# RF-learn-command-1relay.net
KiCad netlist of a schematic drawn in Altium Designer
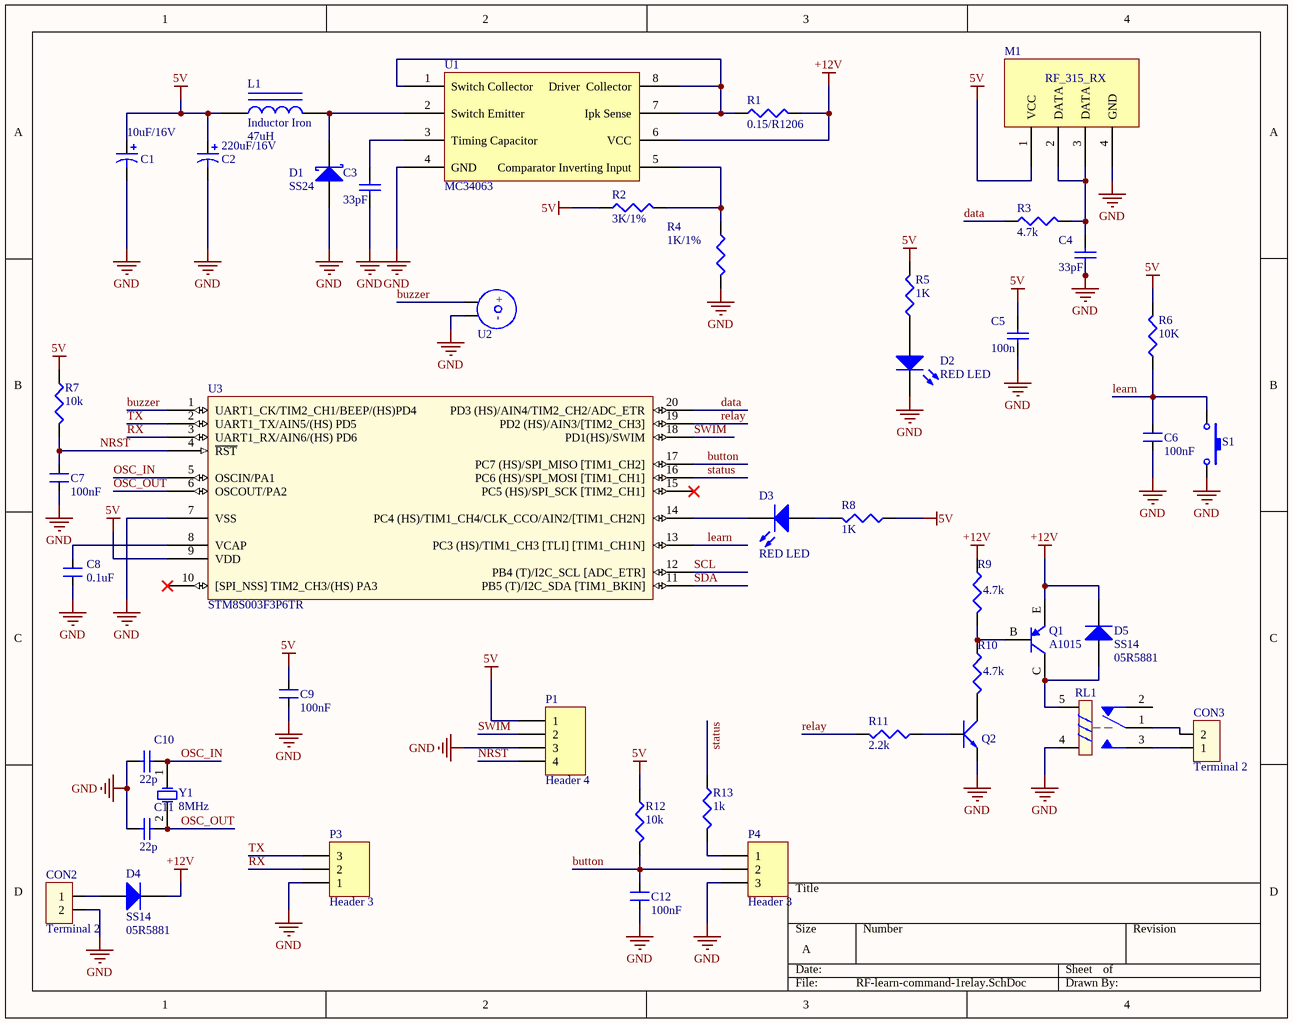
[diagram p0: RF-learn-command-1relay.SchDoc]

(export (version "E")
  (design (tool "Eeschema 10.0.6"))
  (components
    (comp (ref "C1")
      (value "10uF/16V")
      (footprint "Capacitor:C1206")
      (description "Polarized Capacitor (Surface Mount)")
      (fields (field (name "PUBLISHER") "Altium Limited"))
      (libsource (lib "Miscellaneous Devices") (part "Cap Pol3"))
    )
    (comp (ref "C2")
      (value "220uF/16V")
      (footprint "CAPACITOR SIZE_D(D6.6)")
      (description "Polarized Capacitor (Surface Mount)")
      (fields (field (name "PUBLISHER") "Altium Limited"))
      (libsource (lib "Miscellaneous Devices") (part "Cap Pol3"))
    )
    (comp (ref "C3")
      (value "33pF")
      (footprint "ST:CM 0805")
      (description "Capacitor 100n 16V 0603")
      (fields (field (name "PUBLISHER") "Altium Limited"))
      (libsource (lib "Capacitor") (part "Cap Semi"))
    )
    (comp (ref "C4")
      (value "33pF")
      (footprint "ST:CM 0805")
      (description "Capacitor 100n 16V 0603")
      (fields (field (name "PUBLISHER") "Altium Limited"))
      (libsource (lib "Capacitor") (part "Cap Semi"))
    )
    (comp (ref "C5")
      (value "100n")
      (footprint "ST:CM 0805")
      (description "Capacitor 100n 16V 0603")
      (fields (field (name "PUBLISHER") "Altium Limited"))
      (libsource (lib "Capacitor") (part "Cap Semi"))
    )
    (comp (ref "C6")
      (value "100nF")
      (footprint "ST:CM 0805")
      (description "SMD Ceramic  Capacitor")
      (fields (field (name "VOLTAGE") "50V") (field (name "TOLERANCE") "10%"))
      (libsource (lib "ST") (part "CM Ceramic"))
    )
    (comp (ref "C7")
      (value "100nF")
      (footprint "ST:CM 0805")
      (description "SMD Ceramic  Capacitor")
      (fields (field (name "VOLTAGE") "50V") (field (name "TOLERANCE") "10%"))
      (libsource (lib "ST") (part "CM Ceramic"))
    )
    (comp (ref "C8")
      (value "0.1uF")
      (footprint "ST:CM 0805")
      (description "SMD Ceramic  Capacitor")
      (fields (field (name "VOLTAGE") "50V") (field (name "TOLERANCE") "10%"))
      (libsource (lib "ST") (part "CM Ceramic"))
    )
    (comp (ref "C9")
      (value "100nF")
      (footprint "ST:CM 0805")
      (description "SMD Ceramic  Capacitor")
      (fields (field (name "VOLTAGE") "50V") (field (name "TOLERANCE") "10%"))
      (libsource (lib "ST") (part "CM Ceramic"))
    )
    (comp (ref "C10")
      (value "22p")
      (footprint "ST:CM 0805")
      (description "Capacitor (Semiconductor SIM Model)")
      (fields (field (name "PUBLISHER") "Altium Limited"))
      (libsource (lib "Miscellaneous Devices") (part "Cap Semi"))
    )
    (comp (ref "C11")
      (value "22p")
      (footprint "ST:CM 0805")
      (description "Capacitor (Semiconductor SIM Model)")
      (fields (field (name "PUBLISHER") "Altium Limited"))
      (libsource (lib "Miscellaneous Devices") (part "Cap Semi"))
    )
    (comp (ref "C12")
      (value "100nF")
      (footprint "ST:CM 0805")
      (description "SMD Ceramic  Capacitor")
      (fields (field (name "VOLTAGE") "50V") (field (name "TOLERANCE") "10%"))
      (libsource (lib "ST") (part "CM Ceramic"))
    )
    (comp (ref "CON2")
      (value "Terminal 2")
      (footprint "Terminal 2 5.08")
      (libsource (lib "") (part "Terminal 2_1"))
    )
    (comp (ref "CON3")
      (value "Terminal 2")
      (footprint "domino-2pin-7.62")
      (libsource (lib "SS_Con") (part "Terminal 2"))
    )
    (comp (ref "D1")
      (value "SS24")
      (footprint "DO-214AA")
      (description "Schottky Diode")
      (fields (field (name "PUBLISHER") "Altium Limited"))
      (libsource (lib "Miscellaneous Devices") (part "D Schottky"))
    )
    (comp (ref "D2")
      (value "RED LED")
      (footprint "LED3mm-R")
      (description "LED SUPR RED CLR 0805 RT ANG SMD")
      (fields
        (field (name "DIGI-KEY PART NUMBER") "160-1469-2-ND")
        (field (name "MANUFACTURER") "Lite-On Inc")
        (field (name "PUBLISHER") "Altium Limited")
      )
      (libsource (lib "Miscellaneous Devices") (part "LED2"))
    )
    (comp (ref "D3")
      (value "RED LED")
      (footprint "LED3mm-G")
      (description "LED SUPR RED CLR 0805 RT ANG SMD")
      (fields
        (field (name "DIGI-KEY PART NUMBER") "160-1469-2-ND")
        (field (name "MANUFACTURER") "Lite-On Inc")
        (field (name "PUBLISHER") "Altium Limited")
      )
      (libsource (lib "Miscellaneous Devices") (part "LED2"))
    )
    (comp (ref "D4")
      (value "SS14")
      (footprint "DO-214AC (SMA)")
      (description "DIODE GEN PURPOSE 1000V 1A SMA")
      (fields
        (field (name "DIGI-KEY PART NUMBER") "641-1018-1-ND")
        (field (name "MANUFACTURER PART NUMBER") "CGRA4007-G")
        (field (name "SUPPLIER PART NUMBER 1") "05R5881")
        (field (name "PUBLISHER") "Altium Limited")
      )
      (libsource (lib "Miscellaneous Devices") (part "Diode"))
    )
    (comp (ref "D5")
      (value "SS14")
      (footprint "DO-214AC (SMA)")
      (description "DIODE GEN PURPOSE 1000V 1A SMA")
      (fields
        (field (name "DIGI-KEY PART NUMBER") "641-1018-1-ND")
        (field (name "MANUFACTURER PART NUMBER") "CGRA4007-G")
        (field (name "SUPPLIER PART NUMBER 1") "05R5881")
        (field (name "PUBLISHER") "Altium Limited")
      )
      (libsource (lib "Miscellaneous Devices") (part "Diode"))
    )
    (comp (ref "L1")
      (value "Inductor Iron")
      (footprint "4848")
      (description "Magnetic-Core Inductor")
      (fields (field (name "ALTIUM_VALUE") "47uH") (field (name "PUBLISHER") "Altium Limited"))
      (libsource (lib "Schematic") (part "Inductor Iron"))
    )
    (comp (ref "M1")
      (value "RF_315_RX")
      (footprint "module-lib:Module-RF-RX")
      (libsource (lib "module-lib") (part "ModuleRF-RX"))
    )
    (comp (ref "P1")
      (value "Header 4")
      (footprint "SS_Con:HDR1X4")
      (description "Header, 4-Pin")
      (fields (field (name "PUBLISHER") "Altium Limited"))
      (libsource (lib "SS_Con") (part "Header 4"))
    )
    (comp (ref "P3")
      (value "Header 3")
      (footprint "SS_Con:HDR1X3")
      (description "Header, 3-Pin")
      (fields (field (name "PUBLISHER") "Altium Limited"))
      (libsource (lib "SS_Con") (part "Header 3"))
    )
    (comp (ref "P4")
      (value "Header 3")
      (footprint "HEADER_3_W")
      (description "Header, 3-Pin")
      (fields (field (name "PUBLISHER") "Altium Limited"))
      (libsource (lib "") (part "Header 3_1"))
    )
    (comp (ref "Q1")
      (value "A1015")
      (footprint "SC-43-BCE")
      (libsource (lib "Transistor") (part "PNP Transistor"))
    )
    (comp (ref "Q2")
      (value "C1815")
      (footprint "2SC1815")
      (description "NPN SMD Transistor")
      (fields (field (name "MANUFACTURER") "Toshiba"))
      (libsource (lib "ST") (part "C1815"))
    )
    (comp (ref "R1")
      (value "0.15/R1206")
      (footprint "R1206")
      (description "Resistor 10k 0603")
      (fields (field (name "PUBLISHER") "Altium Limited"))
      (libsource (lib "Miscellaneous Devices") (part "Res3"))
    )
    (comp (ref "R2")
      (value "3K/1%")
      (footprint "R0805")
      (description "Resistor 10k 0603")
      (fields (field (name "PUBLISHER") "Altium Limited"))
      (libsource (lib "Miscellaneous Devices") (part "Res3"))
    )
    (comp (ref "R3")
      (value "4.7k")
      (footprint "R0805")
      (description "Resistor")
      (fields
        (field (name "MANUFACTURER") "Vishay / Draloric")
        (field (name "MANUFACTURER PART NUMBER") "RCV0805301KFKEA")
        (field (name "PUBLISHER") "Altium Limited")
      )
      (libsource (lib "altium-import") (part "root_0_Res3_"))
    )
    (comp (ref "R4")
      (value "1K/1%")
      (footprint "R0805")
      (description "Resistor 10k 0603")
      (fields (field (name "PUBLISHER") "Altium Limited"))
      (libsource (lib "Miscellaneous Devices") (part "Res3"))
    )
    (comp (ref "R5")
      (value "1K")
      (footprint "R0805")
      (description "Resistor 10k 0603")
      (fields (field (name "PUBLISHER") "Altium Limited"))
      (libsource (lib "Miscellaneous Devices") (part "Res3"))
    )
    (comp (ref "R6")
      (value "10K")
      (footprint "R0805")
      (description "Resistor 10k 0603")
      (fields (field (name "PUBLISHER") "Altium Limited"))
      (libsource (lib "Miscellaneous Devices") (part "Res3"))
    )
    (comp (ref "R7")
      (value "10k")
      (footprint "R0805")
      (description "Resistor")
      (fields
        (field (name "MANUFACTURER") "Vishay / Draloric")
        (field (name "MANUFACTURER PART NUMBER") "RCV0805301KFKEA")
        (field (name "PUBLISHER") "Altium Limited")
      )
      (libsource (lib "altium-import") (part "root_3_Res3_"))
    )
    (comp (ref "R8")
      (value "1K")
      (footprint "R0805")
      (description "Resistor 10k 0603")
      (fields (field (name "PUBLISHER") "Altium Limited"))
      (libsource (lib "Miscellaneous Devices") (part "Res3"))
    )
    (comp (ref "R9")
      (value "4.7k")
      (footprint "R0805")
      (description "Resistor")
      (fields
        (field (name "MANUFACTURER") "Vishay / Draloric")
        (field (name "MANUFACTURER PART NUMBER") "RCV0805301KFKEA")
        (field (name "PUBLISHER") "Altium Limited")
      )
      (libsource (lib "altium-import") (part "root_3_Res3_"))
    )
    (comp (ref "R10")
      (value "4.7k")
      (footprint "R0805")
      (description "Resistor")
      (fields
        (field (name "MANUFACTURER") "Vishay / Draloric")
        (field (name "MANUFACTURER PART NUMBER") "RCV0805301KFKEA")
        (field (name "PUBLISHER") "Altium Limited")
      )
      (libsource (lib "altium-import") (part "root_3_Res3_"))
    )
    (comp (ref "R11")
      (value "2.2k")
      (footprint "R0805")
      (description "Resistor")
      (fields
        (field (name "MANUFACTURER") "Vishay / Draloric")
        (field (name "MANUFACTURER PART NUMBER") "RCV0805301KFKEA")
        (field (name "PUBLISHER") "Altium Limited")
      )
      (libsource (lib "altium-import") (part "root_2_Res3_"))
    )
    (comp (ref "R12")
      (value "10k")
      (footprint "R0805")
      (description "Resistor")
      (fields
        (field (name "MANUFACTURER") "Vishay / Draloric")
        (field (name "MANUFACTURER PART NUMBER") "RCV0805301KFKEA")
        (field (name "PUBLISHER") "Altium Limited")
      )
      (libsource (lib "altium-import") (part "root_3_Res3_"))
    )
    (comp (ref "R13")
      (value "1k")
      (footprint "R0805")
      (description "Resistor")
      (fields
        (field (name "MANUFACTURER") "Vishay / Draloric")
        (field (name "MANUFACTURER PART NUMBER") "RCV0805301KFKEA")
        (field (name "PUBLISHER") "Altium Limited")
      )
      (libsource (lib "altium-import") (part "root_3_Res3_"))
    )
    (comp (ref "RL1")
      (value "Relay SPDT, 10A, 12V")
      (footprint "RL-SLA-24/12VDC-SL-C")
      (description "Relay SPDT,10A - 12VDC 5 Pin")
      (libsource (lib "nhantt-relay-lib") (part "Relay 1"))
    )
    (comp (ref "S1")
      (value "SW-SMD")
      (footprint "Button Tactile Switch")
      (description "Switch")
      (fields (field (name "PUBLISHER") "Altium Limited"))
      (libsource (lib "Schematic") (part "SW-SMD"))
    )
    (comp (ref "U1")
      (value "MC34063")
      (footprint "SO8-150mil")
      (libsource (lib "General IC") (part "MC34063"))
    )
    (comp (ref "U2") (value "Buzzer") (footprint "Buzzer") (libsource (lib "ST") (part "Buzzer")))
    (comp (ref "U3")
      (value "STM8S003F3P6TR")
      (footprint "SSOP-20")
      (description "MCU")
      (fields (field (name "MANUFACTURER") "STMicroelectronics"))
      (libsource (lib "mcu-lib") (part "STM8S003F3"))
    )
    (comp (ref "Y1")
      (value "8MHz")
      (footprint "XTAL:HC49/US-SMD")
      (description "Crystal Oscillator")
      (fields (field (name "PUBLISHER") "Altium Limited"))
      (libsource (lib "Miscellaneous Devices") (part "XTAL"))
    )
  )
  (nets
    (net (code "1") (name "+12V") (class "Default")
      (node (ref "D4") (pin "2") (pinfunction "K_2") (pintype "passive"))
      (node (ref "D5") (pin "2") (pinfunction "K_2") (pintype "passive"))
      (node (ref "Q1") (pin "E") (pinfunction "E_E") (pintype "passive"))
      (node (ref "R1") (pin "2") (pinfunction "2_2") (pintype "passive"))
      (node (ref "R9") (pin "1") (pinfunction "1_1") (pintype "passive"))
      (node (ref "U1") (pin "6") (pinfunction "VCC_6") (pintype "passive"))
    )
    (net (code "2") (name "/NRST") (class "Default")
      (node (ref "C7") (pin "2") (pinfunction "2_2") (pintype "passive"))
      (node (ref "P1") (pin "4") (pinfunction "4_4") (pintype "passive"))
      (node (ref "R7") (pin "2") (pinfunction "2_2") (pintype "passive"))
      (node (ref "U3") (pin "4") (pinfunction "~{RST}_4") (pintype "input"))
    )
    (net (code "3") (name "/OSC_IN") (class "Default")
      (node (ref "C10") (pin "2") (pinfunction "2_2") (pintype "passive"))
      (node (ref "U3") (pin "5") (pinfunction "OSCIN/PA1_5") (pintype "bidirectional"))
      (node (ref "Y1") (pin "1") (pinfunction "OSC1_1") (pintype "passive"))
    )
    (net (code "4") (name "/OSC_OUT") (class "Default")
      (node (ref "C11") (pin "2") (pinfunction "2_2") (pintype "passive"))
      (node (ref "U3") (pin "6") (pinfunction "OSCOUT/PA2_6") (pintype "bidirectional"))
      (node (ref "Y1") (pin "2") (pinfunction "OSC2_2") (pintype "passive"))
    )
    (net (code "5") (name "/RX") (class "Default")
      (node (ref "P3") (pin "2") (pinfunction "2_2") (pintype "passive"))
      (node (ref "U3") (pin "3") (pinfunction "UART1_RX/AIN6/(HS)_PD6_3") (pintype "bidirectional"))
    )
    (net (code "6") (name "/SCL") (class "Default")
      (node (ref "U3") (pin "12") (pinfunction "PB4_(T)/I2C_SCL_[ADC_ETR]_12") (pintype "bidirectional"))
    )
    (net (code "7") (name "/SDA") (class "Default")
      (node (ref "U3") (pin "11") (pinfunction "PB5_(T)/I2C_SDA_[TIM1_BKIN]_11") (pintype "bidirectional"))
    )
    (net (code "8") (name "/SWIM") (class "Default")
      (node (ref "P1") (pin "2") (pinfunction "2_2") (pintype "passive"))
      (node (ref "U3") (pin "18") (pinfunction "PD1(HS)/SWIM_18") (pintype "bidirectional"))
    )
    (net (code "9") (name "/TX") (class "Default")
      (node (ref "P3") (pin "3") (pinfunction "3_3") (pintype "passive"))
      (node (ref "U3") (pin "2") (pinfunction "UART1_TX/AIN5/(HS)_PD5_2") (pintype "bidirectional"))
    )
    (net (code "10") (name "/button") (class "Default")
      (node (ref "C12") (pin "2") (pinfunction "2_2") (pintype "passive"))
      (node (ref "P4") (pin "2") (pinfunction "2_2") (pintype "passive"))
      (node (ref "R12") (pin "2") (pinfunction "2_2") (pintype "passive"))
      (node (ref "U3") (pin "17") (pinfunction "PC7_(HS)/SPI_MISO_[TIM1_CH2]_17") (pintype "bidirectional"))
    )
    (net (code "11") (name "/buzzer") (class "Default")
      (node (ref "U2") (pin "1") (pinfunction "1_1") (pintype "passive"))
      (node (ref "U3") (pin "1") (pinfunction "UART1_CK/TIM2_CH1/BEEP/(HS)PD4_1") (pintype "bidirectional"))
    )
    (net (code "12") (name "/data") (class "Default")
      (node (ref "R3") (pin "1") (pinfunction "1_1") (pintype "passive"))
      (node (ref "U3") (pin "20") (pinfunction "PD3_(HS)/AIN4/TIM2_CH2/ADC_ETR_20") (pintype "bidirectional"))
    )
    (net (code "13") (name "/learn") (class "Default")
      (node (ref "C6") (pin "2") (pinfunction "2_2") (pintype "passive"))
      (node (ref "R6") (pin "1") (pinfunction "1_1") (pintype "passive"))
      (node (ref "S1") (pin "1") (pinfunction "1_1") (pintype "passive"))
      (node (ref "U3") (pin "13") (pinfunction "PC3_(HS)/TIM1_CH3_[TLI]_[TIM1_CH1N]_13") (pintype "bidirectional"))
    )
    (net (code "14") (name "/relay") (class "Default")
      (node (ref "R11") (pin "2") (pinfunction "2_2") (pintype "passive"))
      (node (ref "U3") (pin "19") (pinfunction "PD2_(HS)/AIN3/[TIM2_CH3]_19") (pintype "bidirectional"))
    )
    (net (code "15") (name "/status") (class "Default")
      (node (ref "R13") (pin "1") (pinfunction "1_1") (pintype "passive"))
      (node (ref "U3") (pin "16") (pinfunction "PC6_(HS)/SPI_MOSI_[TIM1_CH1]_16") (pintype "bidirectional"))
    )
    (net (code "16") (name "5V") (class "Default")
      (node (ref "C1") (pin "1") (pinfunction "1_1") (pintype "passive"))
      (node (ref "C2") (pin "1") (pinfunction "1_1") (pintype "passive"))
      (node (ref "C5") (pin "1") (pinfunction "1_1") (pintype "passive"))
      (node (ref "C9") (pin "2") (pinfunction "2_2") (pintype "passive"))
      (node (ref "L1") (pin "1") (pinfunction "1_1") (pintype "passive"))
      (node (ref "M1") (pin "1") (pinfunction "VCC_1") (pintype "passive"))
      (node (ref "P1") (pin "1") (pinfunction "1_1") (pintype "passive"))
      (node (ref "R12") (pin "1") (pinfunction "1_1") (pintype "passive"))
      (node (ref "R2") (pin "1") (pinfunction "1_1") (pintype "passive"))
      (node (ref "R5") (pin "2") (pinfunction "2_2") (pintype "passive"))
      (node (ref "R6") (pin "2") (pinfunction "2_2") (pintype "passive"))
      (node (ref "R7") (pin "1") (pinfunction "1_1") (pintype "passive"))
      (node (ref "R8") (pin "1") (pinfunction "1_1") (pintype "passive"))
      (node (ref "U3") (pin "9") (pinfunction "VDD_9") (pintype "power_in"))
    )
    (net (code "17") (name "GND") (class "Default")
      (node (ref "C1") (pin "2") (pinfunction "2_2") (pintype "passive"))
      (node (ref "C10") (pin "1") (pinfunction "1_1") (pintype "passive"))
      (node (ref "C11") (pin "1") (pinfunction "1_1") (pintype "passive"))
      (node (ref "C12") (pin "1") (pinfunction "1_1") (pintype "passive"))
      (node (ref "C2") (pin "2") (pinfunction "2_2") (pintype "passive"))
      (node (ref "C3") (pin "2") (pinfunction "2_2") (pintype "passive"))
      (node (ref "C4") (pin "2") (pinfunction "2_2") (pintype "passive"))
      (node (ref "C5") (pin "2") (pinfunction "2_2") (pintype "passive"))
      (node (ref "C6") (pin "1") (pinfunction "1_1") (pintype "passive"))
      (node (ref "C7") (pin "1") (pinfunction "1_1") (pintype "passive"))
      (node (ref "C8") (pin "1") (pinfunction "1_1") (pintype "passive"))
      (node (ref "C9") (pin "1") (pinfunction "1_1") (pintype "passive"))
      (node (ref "CON2") (pin "2") (pinfunction "2_2") (pintype "passive"))
      (node (ref "D1") (pin "1") (pinfunction "A_1") (pintype "passive"))
      (node (ref "D2") (pin "2") (pinfunction "K_2") (pintype "passive"))
      (node (ref "M1") (pin "4") (pinfunction "GND_4") (pintype "passive"))
      (node (ref "P1") (pin "3") (pinfunction "3_3") (pintype "passive"))
      (node (ref "P3") (pin "1") (pinfunction "1_1") (pintype "passive"))
      (node (ref "P4") (pin "3") (pinfunction "3_3") (pintype "passive"))
      (node (ref "Q2") (pin "2") (pinfunction "E_2") (pintype "passive"))
      (node (ref "R4") (pin "2") (pinfunction "2_2") (pintype "passive"))
      (node (ref "RL1") (pin "4") (pinfunction "4_4") (pintype "passive"))
      (node (ref "S1") (pin "2") (pinfunction "2_2") (pintype "passive"))
      (node (ref "U1") (pin "4") (pinfunction "GND_4") (pintype "passive"))
      (node (ref "U2") (pin "2") (pinfunction "2_2") (pintype "passive"))
      (node (ref "U3") (pin "7") (pinfunction "VSS_7") (pintype "power_in"))
    )
    (net (code "18") (name "Net-(C4-Pad1)") (class "Default")
      (node (ref "C4") (pin "1") (pinfunction "1_1") (pintype "passive"))
      (node (ref "M1") (pin "2") (pinfunction "DATA_2") (pintype "passive"))
      (node (ref "M1") (pin "3") (pinfunction "DATA_3") (pintype "passive"))
      (node (ref "R3") (pin "2") (pinfunction "2_2") (pintype "passive"))
    )
    (net (code "19") (name "Net-(CON3-Pad1)") (class "Default")
      (node (ref "CON3") (pin "1") (pinfunction "1_1") (pintype "passive"))
      (node (ref "RL1") (pin "3") (pinfunction "3_3") (pintype "passive"))
    )
    (net (code "20") (name "Net-(CON3-Pad2)") (class "Default")
      (node (ref "CON3") (pin "2") (pinfunction "2_2") (pintype "passive"))
      (node (ref "RL1") (pin "1") (pinfunction "1_1") (pintype "passive"))
    )
    (net (code "21") (name "Net-(D1-K)") (class "Default")
      (node (ref "D1") (pin "2") (pinfunction "K_2") (pintype "passive"))
      (node (ref "L1") (pin "2") (pinfunction "2_2") (pintype "passive"))
      (node (ref "U1") (pin "2") (pinfunction "Switch_Emitter_2") (pintype "passive"))
    )
    (net (code "22") (name "Net-(D2-A)") (class "Default")
      (node (ref "D2") (pin "1") (pinfunction "A_1") (pintype "passive"))
      (node (ref "R5") (pin "1") (pinfunction "1_1") (pintype "passive"))
    )
    (net (code "23") (name "Net-(D3-A)") (class "Default")
      (node (ref "D3") (pin "1") (pinfunction "A_1") (pintype "passive"))
      (node (ref "R8") (pin "2") (pinfunction "2_2") (pintype "passive"))
    )
    (net (code "24") (name "Net-(D3-K)") (class "Default")
      (node (ref "D3") (pin "2") (pinfunction "K_2") (pintype "passive"))
      (node (ref "U3") (pin "14") (pinfunction "PC4_(HS)/TIM1_CH4/CLK_CCO/AIN2/[TIM1_CH2N]_14") (pintype "bidirectional"))
    )
    (net (code "25") (name "Net-(D4-A)") (class "Default")
      (node (ref "CON2") (pin "1") (pinfunction "1_1") (pintype "passive"))
      (node (ref "D4") (pin "1") (pinfunction "A_1") (pintype "passive"))
    )
    (net (code "26") (name "Net-(D5-A)") (class "Default")
      (node (ref "D5") (pin "1") (pinfunction "A_1") (pintype "passive"))
      (node (ref "Q1") (pin "C") (pinfunction "C_C") (pintype "passive"))
      (node (ref "RL1") (pin "5") (pinfunction "5_5") (pintype "passive"))
    )
    (net (code "27") (name "Net-(P4-Pad1)") (class "Default")
      (node (ref "P4") (pin "1") (pinfunction "1_1") (pintype "passive"))
      (node (ref "R13") (pin "2") (pinfunction "2_2") (pintype "passive"))
    )
    (net (code "28") (name "Net-(Q1-PadB)") (class "Default")
      (node (ref "Q1") (pin "B") (pinfunction "B_B") (pintype "passive"))
      (node (ref "R10") (pin "1") (pinfunction "1_1") (pintype "passive"))
      (node (ref "R9") (pin "2") (pinfunction "2_2") (pintype "passive"))
    )
    (net (code "29") (name "Net-(Q2-B)") (class "Default")
      (node (ref "Q2") (pin "1") (pinfunction "B_1") (pintype "passive"))
      (node (ref "R11") (pin "1") (pinfunction "1_1") (pintype "passive"))
    )
    (net (code "30") (name "Net-(Q2-C)") (class "Default")
      (node (ref "Q2") (pin "3") (pinfunction "C_3") (pintype "passive"))
      (node (ref "R10") (pin "2") (pinfunction "2_2") (pintype "passive"))
    )
    (net (code "31") (name "Net-(U1-Comparator_Inverting_Input)") (class "Default")
      (node (ref "R2") (pin "2") (pinfunction "2_2") (pintype "passive"))
      (node (ref "R4") (pin "1") (pinfunction "1_1") (pintype "passive"))
      (node (ref "U1") (pin "5") (pinfunction "Comparator_Inverting_Input_5") (pintype "passive"))
    )
    (net (code "32") (name "Net-(U1-Driver__Collector)") (class "Default")
      (node (ref "R1") (pin "1") (pinfunction "1_1") (pintype "passive"))
      (node (ref "U1") (pin "1") (pinfunction "Switch_Collector_1") (pintype "passive"))
      (node (ref "U1") (pin "7") (pinfunction "Ipk_Sense_7") (pintype "passive"))
      (node (ref "U1") (pin "8") (pinfunction "Driver__Collector_8") (pintype "passive"))
    )
    (net (code "33") (name "Net-(U1-Timing_Capacitor)") (class "Default")
      (node (ref "C3") (pin "1") (pinfunction "1_1") (pintype "passive"))
      (node (ref "U1") (pin "3") (pinfunction "Timing_Capacitor_3") (pintype "passive"))
    )
    (net (code "34") (name "Net-(U3-VCAP)") (class "Default")
      (node (ref "C8") (pin "2") (pinfunction "2_2") (pintype "passive"))
      (node (ref "U3") (pin "8") (pinfunction "VCAP_8") (pintype "power_in"))
    )
    (net (code "35") (name "unconnected-(RL1-Pad2)") (class "Default")
      (node (ref "RL1") (pin "2") (pinfunction "2_2") (pintype "passive"))
    )
    (net (code "36") (name "unconnected-(U3-PC5_(HS){slash}SPI_SCK_[TIM2_CH1]-Pad15)") (class "Default")
      (node (ref "U3") (pin "15") (pinfunction "PC5_(HS)/SPI_SCK_[TIM2_CH1]_15") (pintype "bidirectional+no_connect"))
    )
    (net (code "37") (name "unconnected-(U3-[SPI_NSS]_TIM2_CH3{slash}(HS)_PA3-Pad10)") (class "Default")
      (node (ref "U3") (pin "10") (pinfunction "[SPI_NSS]_TIM2_CH3/(HS)_PA3_10") (pintype "bidirectional+no_connect"))
    )
  )
)
